# controller.net
KiCad netlist of a schematic drawn in EAGLE
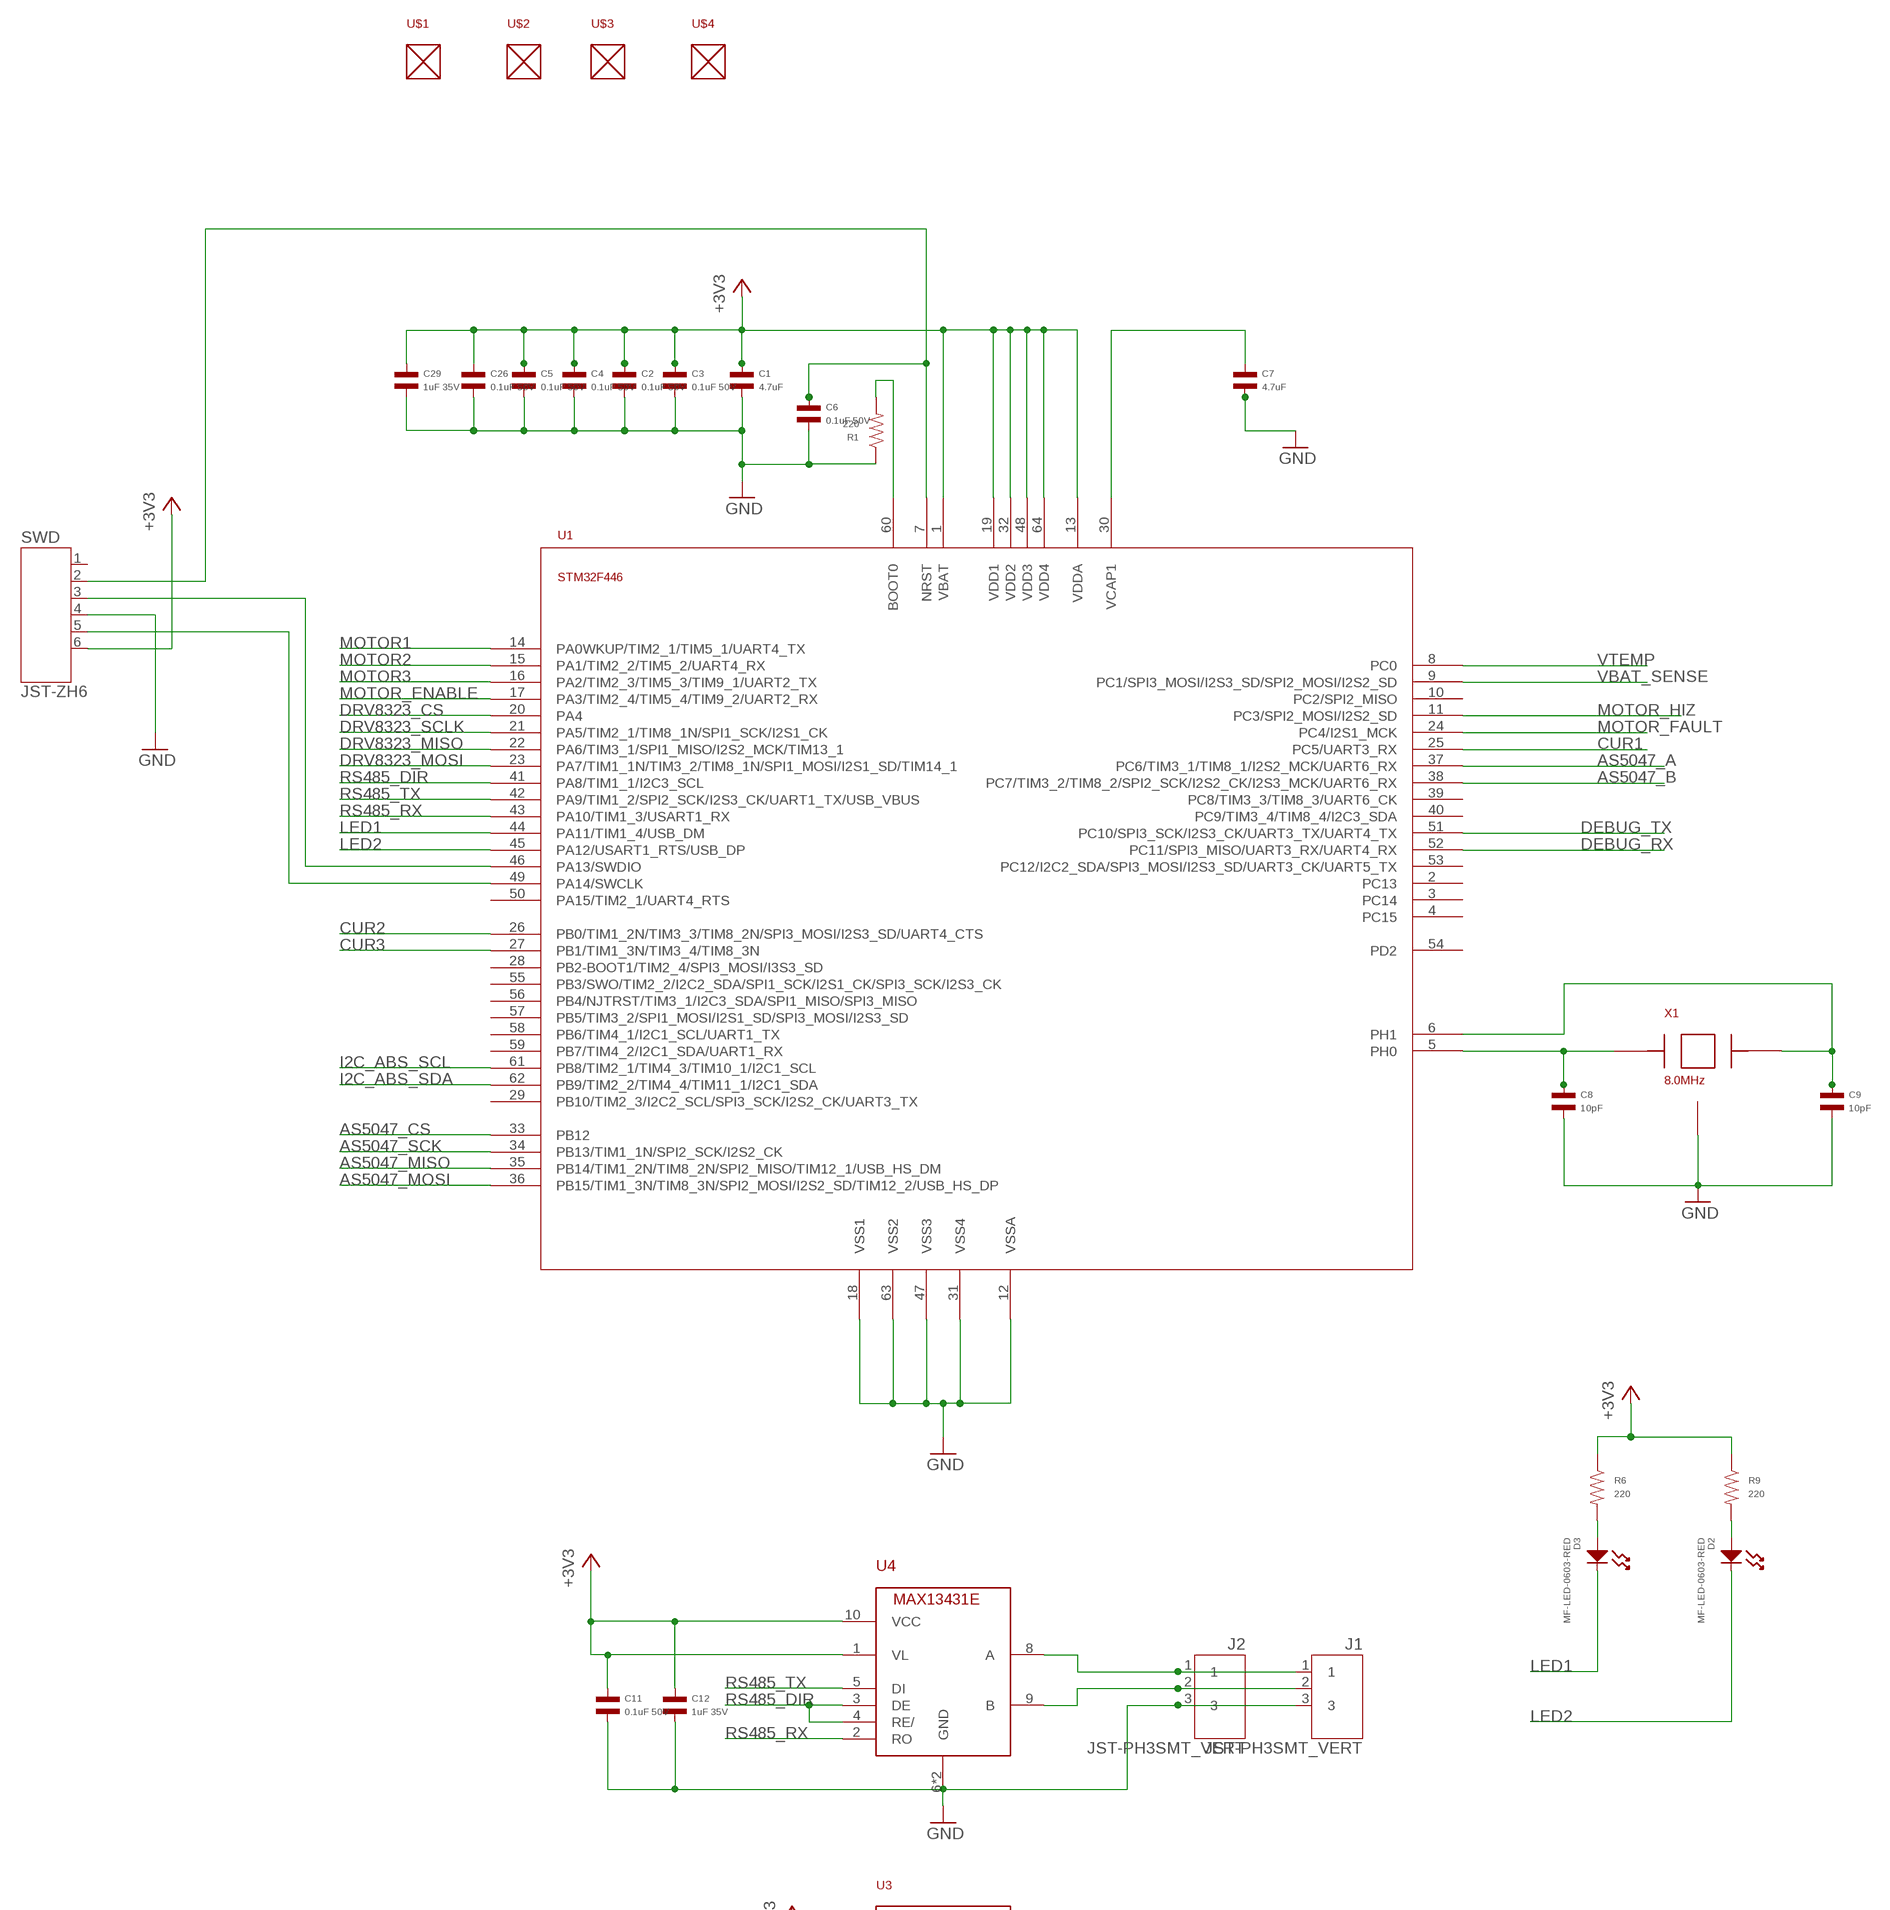
[diagram p0: schematic, sheet 1, part 1 of 2]
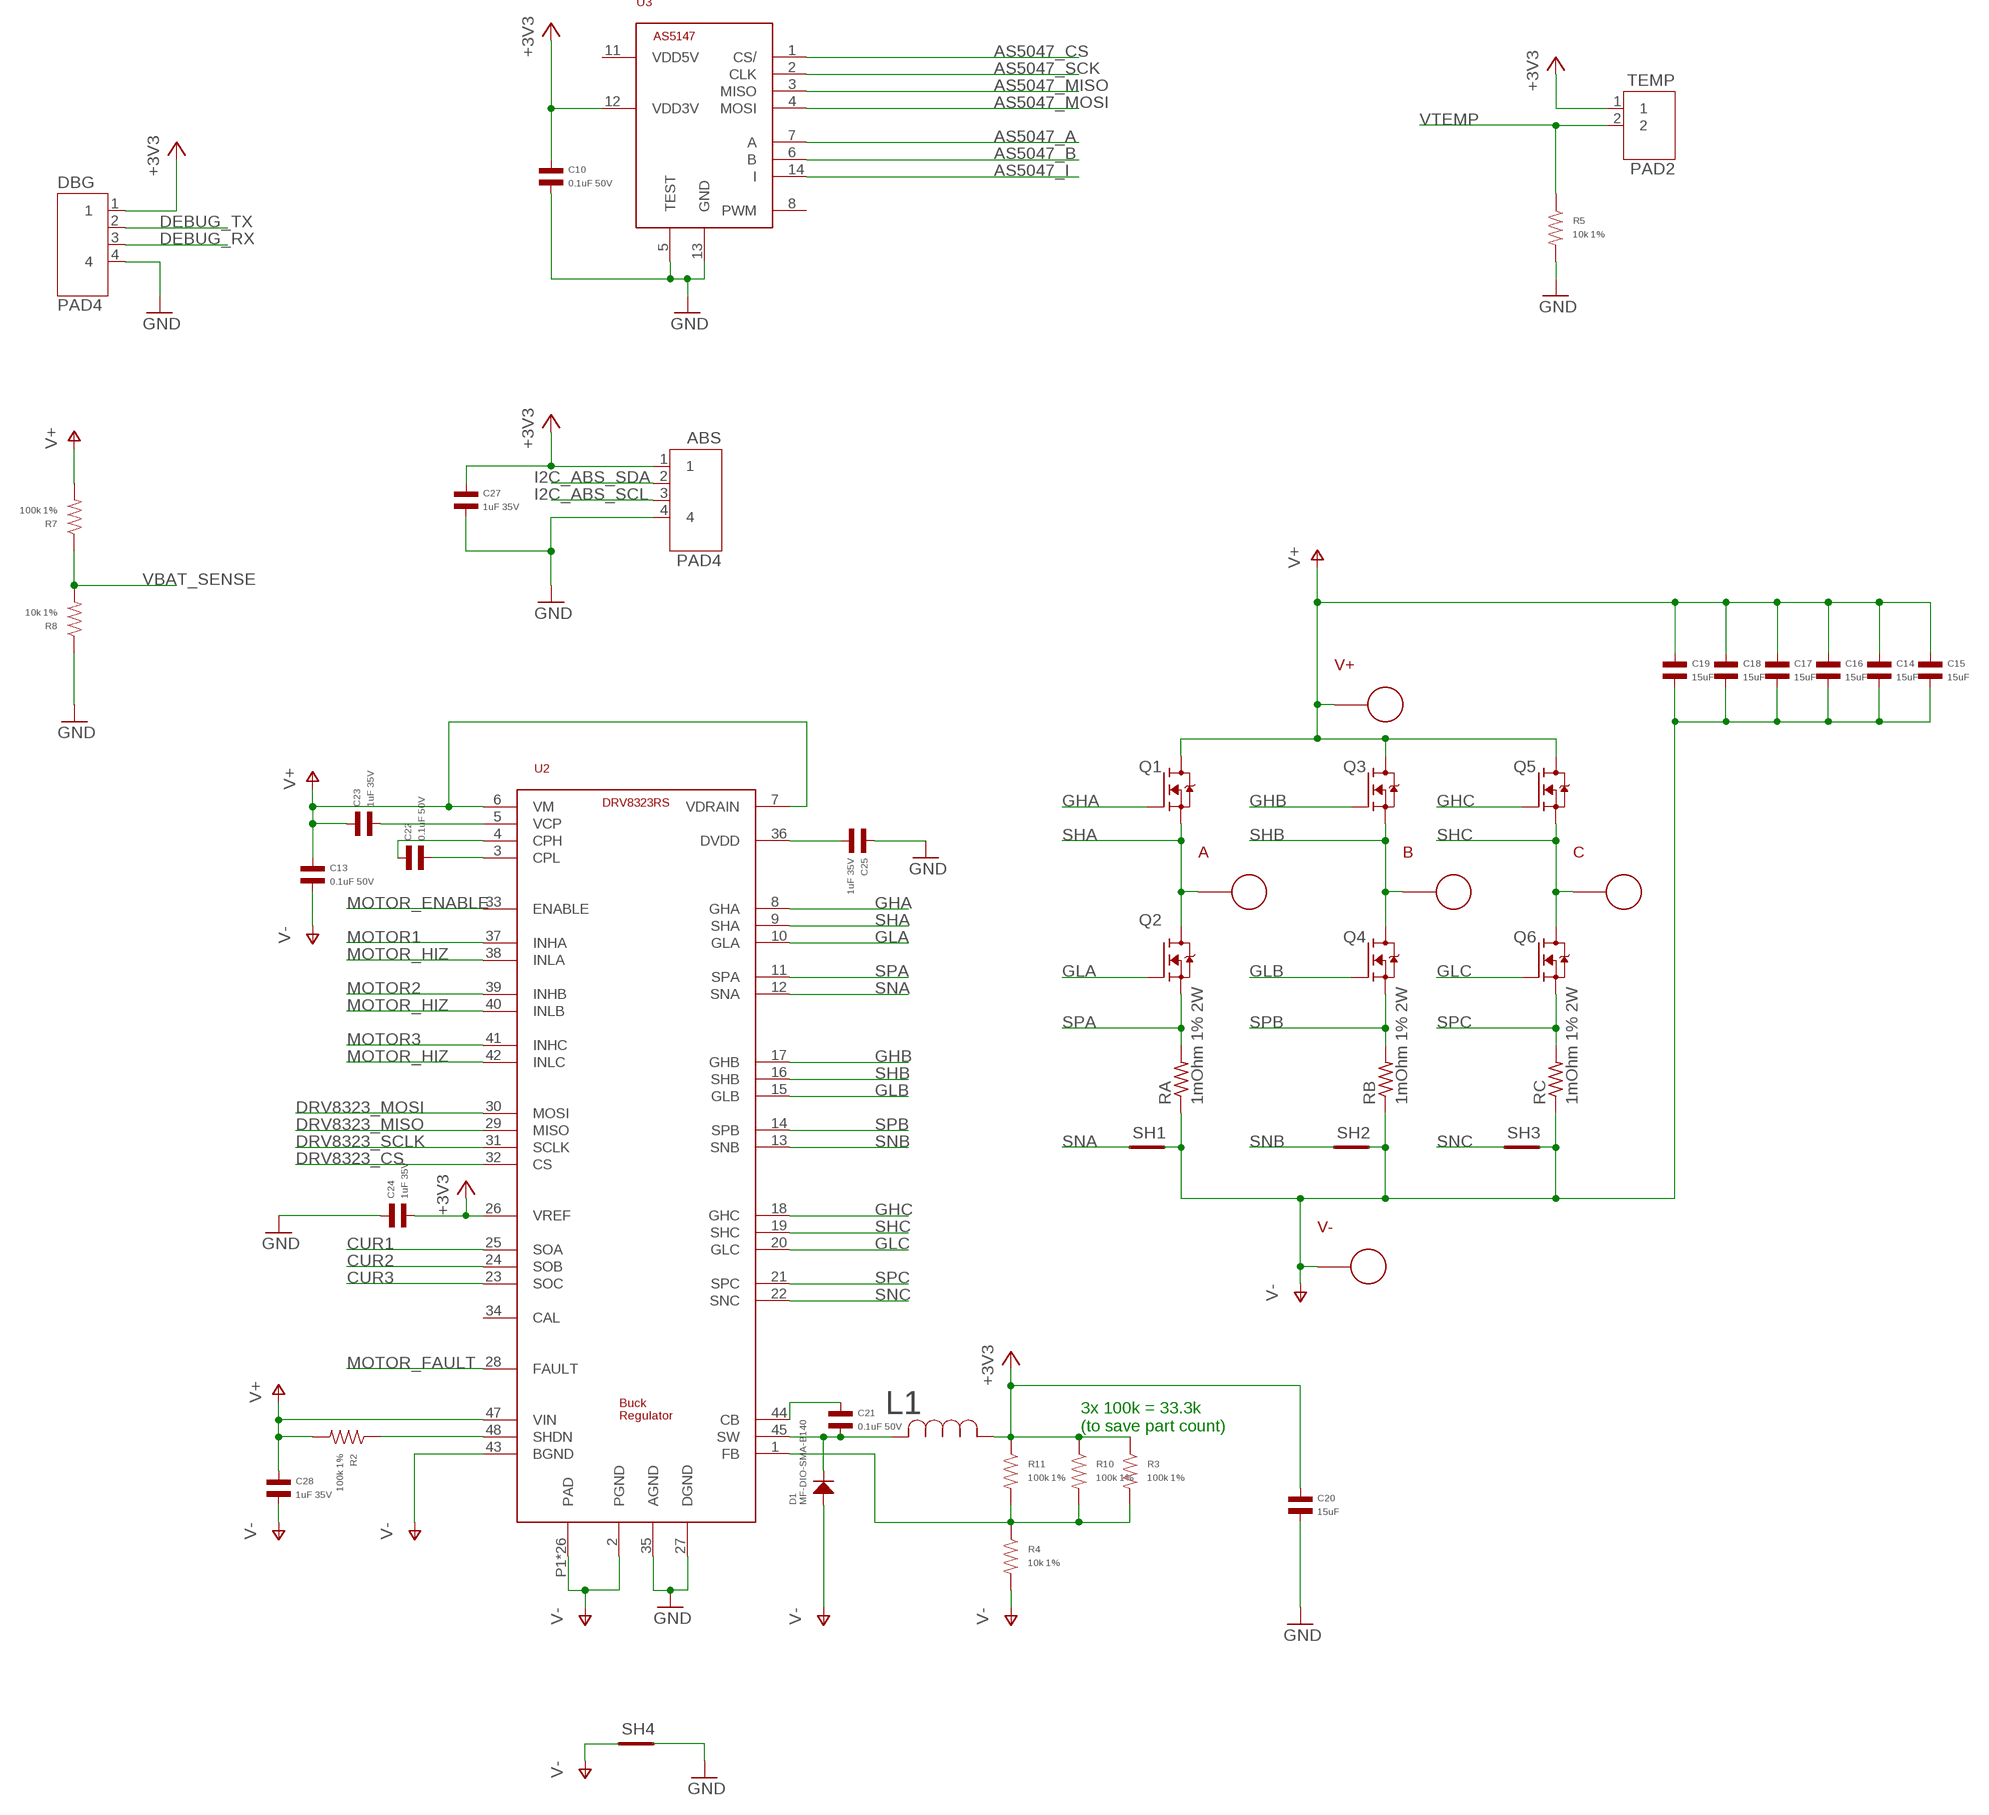
[diagram p1: schematic, sheet 1, part 2 of 2]

(export (version "E")
  (design (tool "Eeschema 10.0.6"))
  (components
    (comp (ref "A")
      (value "PAD")
      (footprint "eagle-import:18AWG_PAD")
      (libsource (lib "eagle-import") (part "PAD"))
    )
    (comp (ref "ABS")
      (value "PAD4")
      (footprint "eagle-import:PAD15_4")
      (libsource (lib "eagle-import") (part "PAD4"))
    )
    (comp (ref "B")
      (value "PAD")
      (footprint "eagle-import:18AWG_PAD")
      (libsource (lib "eagle-import") (part "PAD"))
    )
    (comp (ref "C")
      (value "PAD")
      (footprint "eagle-import:18AWG_PAD")
      (libsource (lib "eagle-import") (part "PAD"))
    )
    (comp (ref "C1")
      (value "4.7uF")
      (footprint "eagle-import:C0603")
      (fields (field (name "MF") "Samsung Electro-Mechanics") (field (name "MPN") "CL10A475MP8NNNC"))
      (libsource (lib "eagle-import") (part "CAPACITOR_NP_0603"))
    )
    (comp (ref "C2")
      (value "0.1uF 50V")
      (footprint "eagle-import:C0402")
      (fields (field (name "MF") "TDK") (field (name "MPN") "C1005X7R1H104K050BE"))
      (libsource (lib "eagle-import") (part "CAPACITOR_NP_0402"))
    )
    (comp (ref "C3")
      (value "0.1uF 50V")
      (footprint "eagle-import:C0402")
      (fields (field (name "MF") "TDK") (field (name "MPN") "C1005X7R1H104K050BE"))
      (libsource (lib "eagle-import") (part "CAPACITOR_NP_0402"))
    )
    (comp (ref "C4")
      (value "0.1uF 50V")
      (footprint "eagle-import:C0402")
      (fields (field (name "MF") "TDK") (field (name "MPN") "C1005X7R1H104K050BE"))
      (libsource (lib "eagle-import") (part "CAPACITOR_NP_0402"))
    )
    (comp (ref "C5")
      (value "0.1uF 50V")
      (footprint "eagle-import:C0402")
      (fields (field (name "MF") "TDK") (field (name "MPN") "C1005X7R1H104K050BE"))
      (libsource (lib "eagle-import") (part "CAPACITOR_NP_0402"))
    )
    (comp (ref "C6")
      (value "0.1uF 50V")
      (footprint "eagle-import:C0402")
      (fields (field (name "MF") "TDK") (field (name "MPN") "C1005X7R1H104K050BE"))
      (libsource (lib "eagle-import") (part "CAPACITOR_NP_0402"))
    )
    (comp (ref "C7")
      (value "4.7uF")
      (footprint "eagle-import:C0603")
      (fields (field (name "MF") "Samsung Electro-Mechanics") (field (name "MPN") "CL10A475MP8NNNC"))
      (libsource (lib "eagle-import") (part "CAPACITOR_NP_0603"))
    )
    (comp (ref "C8")
      (value "10pF")
      (footprint "eagle-import:C0402")
      (fields (field (name "MF") "Samsung Electro-Mechanics") (field (name "MPN") "CL05C100JB51PNC"))
      (libsource (lib "eagle-import") (part "CAPACITOR_NP_0402"))
    )
    (comp (ref "C9")
      (value "10pF")
      (footprint "eagle-import:C0402")
      (fields (field (name "MF") "Samsung Electro-Mechanics") (field (name "MPN") "CL05C100JB51PNC"))
      (libsource (lib "eagle-import") (part "CAPACITOR_NP_0402"))
    )
    (comp (ref "C10")
      (value "0.1uF 50V")
      (footprint "eagle-import:C0402")
      (fields (field (name "MF") "TDK") (field (name "MPN") "C1005X7R1H104K050BE"))
      (libsource (lib "eagle-import") (part "CAPACITOR_NP_0402"))
    )
    (comp (ref "C11")
      (value "0.1uF 50V")
      (footprint "eagle-import:C0402")
      (fields (field (name "MF") "TDK") (field (name "MPN") "C1005X7R1H104K050BE"))
      (libsource (lib "eagle-import") (part "CAPACITOR_NP_0402"))
    )
    (comp (ref "C12")
      (value "1uF 35V")
      (footprint "eagle-import:C0402")
      (fields (field (name "MF") "Samsung Electro-Mechanics") (field (name "MPN") "CL05A105KL5NRNC"))
      (libsource (lib "eagle-import") (part "CAPACITOR_NP_0402"))
    )
    (comp (ref "C13")
      (value "0.1uF 50V")
      (footprint "eagle-import:C0402")
      (fields (field (name "MF") "TDK") (field (name "MPN") "C1005X7R1H104K050BE"))
      (libsource (lib "eagle-import") (part "CAPACITOR_NP_0402"))
    )
    (comp (ref "C14")
      (value "15uF")
      (footprint "eagle-import:C1206")
      (fields (field (name "MF") "TDK") (field (name "MPN") "C3216X5R1V156M160AC"))
      (libsource (lib "eagle-import") (part "CAPACITOR_NP_1206"))
    )
    (comp (ref "C15")
      (value "15uF")
      (footprint "eagle-import:C1206")
      (fields (field (name "MF") "TDK") (field (name "MPN") "C3216X5R1V156M160AC"))
      (libsource (lib "eagle-import") (part "CAPACITOR_NP_1206"))
    )
    (comp (ref "C16")
      (value "15uF")
      (footprint "eagle-import:C1206")
      (fields (field (name "MF") "TDK") (field (name "MPN") "C3216X5R1V156M160AC"))
      (libsource (lib "eagle-import") (part "CAPACITOR_NP_1206"))
    )
    (comp (ref "C17")
      (value "15uF")
      (footprint "eagle-import:C1206")
      (fields (field (name "MF") "TDK") (field (name "MPN") "C3216X5R1V156M160AC"))
      (libsource (lib "eagle-import") (part "CAPACITOR_NP_1206"))
    )
    (comp (ref "C18")
      (value "15uF")
      (footprint "eagle-import:C1206")
      (fields (field (name "MF") "TDK") (field (name "MPN") "C3216X5R1V156M160AC"))
      (libsource (lib "eagle-import") (part "CAPACITOR_NP_1206"))
    )
    (comp (ref "C19")
      (value "15uF")
      (footprint "eagle-import:C1206")
      (fields (field (name "MF") "TDK") (field (name "MPN") "C3216X5R1V156M160AC"))
      (libsource (lib "eagle-import") (part "CAPACITOR_NP_1206"))
    )
    (comp (ref "C20")
      (value "15uF")
      (footprint "eagle-import:C1206")
      (fields (field (name "MF") "TDK") (field (name "MPN") "C3216X5R1V156M160AC"))
      (libsource (lib "eagle-import") (part "CAPACITOR_NP_1206"))
    )
    (comp (ref "C21")
      (value "0.1uF 50V")
      (footprint "eagle-import:C0402")
      (fields (field (name "MF") "TDK") (field (name "MPN") "C1005X7R1H104K050BE"))
      (libsource (lib "eagle-import") (part "CAPACITOR_NP_0402"))
    )
    (comp (ref "C22")
      (value "0.1uF 50V")
      (footprint "eagle-import:C0402")
      (fields (field (name "MF") "TDK") (field (name "MPN") "C1005X7R1H104K050BE"))
      (libsource (lib "eagle-import") (part "CAPACITOR_NP_0402"))
    )
    (comp (ref "C23")
      (value "1uF 35V")
      (footprint "eagle-import:C0402")
      (fields (field (name "MF") "Samsung Electro-Mechanics") (field (name "MPN") "CL05A105KL5NRNC"))
      (libsource (lib "eagle-import") (part "CAPACITOR_NP_0402"))
    )
    (comp (ref "C24")
      (value "1uF 35V")
      (footprint "eagle-import:C0402")
      (fields (field (name "MF") "Samsung Electro-Mechanics") (field (name "MPN") "CL05A105KL5NRNC"))
      (libsource (lib "eagle-import") (part "CAPACITOR_NP_0402"))
    )
    (comp (ref "C25")
      (value "1uF 35V")
      (footprint "eagle-import:C0402")
      (fields (field (name "MF") "Samsung Electro-Mechanics") (field (name "MPN") "CL05A105KL5NRNC"))
      (libsource (lib "eagle-import") (part "CAPACITOR_NP_0402"))
    )
    (comp (ref "C26")
      (value "0.1uF 50V")
      (footprint "eagle-import:C0402")
      (fields (field (name "MF") "TDK") (field (name "MPN") "C1005X7R1H104K050BE"))
      (libsource (lib "eagle-import") (part "CAPACITOR_NP_0402"))
    )
    (comp (ref "C27")
      (value "1uF 35V")
      (footprint "eagle-import:C0402")
      (fields (field (name "MF") "Samsung Electro-Mechanics") (field (name "MPN") "CL05A105KL5NRNC"))
      (libsource (lib "eagle-import") (part "CAPACITOR_NP_0402"))
    )
    (comp (ref "C28")
      (value "1uF 35V")
      (footprint "eagle-import:C0402")
      (fields (field (name "MF") "Samsung Electro-Mechanics") (field (name "MPN") "CL05A105KL5NRNC"))
      (libsource (lib "eagle-import") (part "CAPACITOR_NP_0402"))
    )
    (comp (ref "C29")
      (value "1uF 35V")
      (footprint "eagle-import:C0402")
      (fields (field (name "MF") "Samsung Electro-Mechanics") (field (name "MPN") "CL05A105KL5NRNC"))
      (libsource (lib "eagle-import") (part "CAPACITOR_NP_0402"))
    )
    (comp (ref "D1")
      (value "MF-DIO-SMA-B140")
      (footprint "eagle-import:SMA")
      (fields (field (name "HOUSEPART") "YES"))
      (libsource (lib "eagle-import") (part "DIODES_SMA_B140"))
    )
    (comp (ref "D2")
      (value "MF-LED-0603-RED")
      (footprint "eagle-import:LED0603")
      (fields (field (name "HOUSEPART") "YES"))
      (libsource (lib "eagle-import") (part "LED_SINGLE-0603-RED"))
    )
    (comp (ref "D3")
      (value "MF-LED-0603-RED")
      (footprint "eagle-import:LED0603")
      (fields (field (name "HOUSEPART") "YES"))
      (libsource (lib "eagle-import") (part "LED_SINGLE-0603-RED"))
    )
    (comp (ref "DBG")
      (value "PAD4")
      (footprint "eagle-import:PAD15_4")
      (libsource (lib "eagle-import") (part "PAD4"))
    )
    (comp (ref "J1")
      (value "JST-PH3SMT_VERT")
      (footprint "eagle-import:JST_B3B_PH-SM4-TB(LF)(SN)")
      (fields (field (name "MF") "JST") (field (name "MPN") "B3B-PH-SM4-TB(LF)(SN)"))
      (libsource (lib "eagle-import") (part "JST-PH3SMT_VERT"))
    )
    (comp (ref "J2")
      (value "JST-PH3SMT_VERT")
      (footprint "eagle-import:JST_B3B_PH-SM4-TB(LF)(SN)")
      (fields (field (name "MF") "JST") (field (name "MPN") "B3B-PH-SM4-TB(LF)(SN)"))
      (libsource (lib "eagle-import") (part "JST-PH3SMT_VERT"))
    )
    (comp (ref "L1")
      (value "SRN4018-220M")
      (footprint "eagle-import:IND_BOURNS_SRN4018")
      (fields (field (name "MANUFACTURER_PART_NUMBER") "SRN4018220M"))
      (libsource (lib "eagle-import") (part "SRN4018-220M"))
    )
    (comp (ref "Q1")
      (value "TPN1R603PL")
      (footprint "eagle-import:TSON_ADVANCE_8")
      (fields (field (name "MF") "Toshiba") (field (name "MPN") "TPN1R603PL,L1Q"))
      (libsource (lib "eagle-import") (part "TPN1R603PL"))
    )
    (comp (ref "Q2")
      (value "TPN1R603PL")
      (footprint "eagle-import:TSON_ADVANCE_8")
      (fields (field (name "MF") "Toshiba") (field (name "MPN") "TPN1R603PL,L1Q"))
      (libsource (lib "eagle-import") (part "TPN1R603PL"))
    )
    (comp (ref "Q3")
      (value "TPN1R603PL")
      (footprint "eagle-import:TSON_ADVANCE_8")
      (fields (field (name "MF") "Toshiba") (field (name "MPN") "TPN1R603PL,L1Q"))
      (libsource (lib "eagle-import") (part "TPN1R603PL"))
    )
    (comp (ref "Q4")
      (value "TPN1R603PL")
      (footprint "eagle-import:TSON_ADVANCE_8")
      (fields (field (name "MF") "Toshiba") (field (name "MPN") "TPN1R603PL,L1Q"))
      (libsource (lib "eagle-import") (part "TPN1R603PL"))
    )
    (comp (ref "Q5")
      (value "TPN1R603PL")
      (footprint "eagle-import:TSON_ADVANCE_8")
      (fields (field (name "MF") "Toshiba") (field (name "MPN") "TPN1R603PL,L1Q"))
      (libsource (lib "eagle-import") (part "TPN1R603PL"))
    )
    (comp (ref "Q6")
      (value "TPN1R603PL")
      (footprint "eagle-import:TSON_ADVANCE_8")
      (fields (field (name "MF") "Toshiba") (field (name "MPN") "TPN1R603PL,L1Q"))
      (libsource (lib "eagle-import") (part "TPN1R603PL"))
    )
    (comp (ref "R1")
      (value "220")
      (footprint "eagle-import:R0402")
      (fields (field (name "HOUSEPART") "1") (field (name "MPN") "MF-RES-0402-220"))
      (libsource (lib "eagle-import") (part "RESISTOR_0402"))
    )
    (comp (ref "R2")
      (value "100k 1%")
      (footprint "eagle-import:R0402")
      (fields (field (name "MF") "Panasonic") (field (name "MPN") "ERJ-2RKF1003X"))
      (libsource (lib "eagle-import") (part "RESISTOR_0402"))
    )
    (comp (ref "R3")
      (value "100k 1%")
      (footprint "eagle-import:R0402")
      (fields (field (name "MF") "Panasonic") (field (name "MPN") "ERJ-2RKF1003X"))
      (libsource (lib "eagle-import") (part "RESISTOR_0402"))
    )
    (comp (ref "R4")
      (value "10k 1%")
      (footprint "eagle-import:R0402")
      (fields (field (name "MF") "Panasonic") (field (name "MPN") "ERJ-2RKF1002X"))
      (libsource (lib "eagle-import") (part "RESISTOR_0402"))
    )
    (comp (ref "R5")
      (value "10k 1%")
      (footprint "eagle-import:R0402")
      (fields (field (name "MF") "Panasonic") (field (name "MPN") "ERJ-2RKF1002X"))
      (libsource (lib "eagle-import") (part "RESISTOR_0402"))
    )
    (comp (ref "R6")
      (value "220")
      (footprint "eagle-import:R0402")
      (fields (field (name "HOUSEPART") "1") (field (name "MPN") "MF-RES-0402-220"))
      (libsource (lib "eagle-import") (part "RESISTOR_0402"))
    )
    (comp (ref "R7")
      (value "100k 1%")
      (footprint "eagle-import:R0402")
      (fields (field (name "MF") "Panasonic") (field (name "MPN") "ERJ-2RKF1003X"))
      (libsource (lib "eagle-import") (part "RESISTOR_0402"))
    )
    (comp (ref "R8")
      (value "10k 1%")
      (footprint "eagle-import:R0402")
      (fields (field (name "MF") "Panasonic") (field (name "MPN") "ERJ-2RKF1002X"))
      (libsource (lib "eagle-import") (part "RESISTOR_0402"))
    )
    (comp (ref "R9")
      (value "220")
      (footprint "eagle-import:R0402")
      (fields (field (name "HOUSEPART") "1") (field (name "MPN") "MF-RES-0402-220"))
      (libsource (lib "eagle-import") (part "RESISTOR_0402"))
    )
    (comp (ref "R10")
      (value "100k 1%")
      (footprint "eagle-import:R0402")
      (fields (field (name "MF") "Panasonic") (field (name "MPN") "ERJ-2RKF1003X"))
      (libsource (lib "eagle-import") (part "RESISTOR_0402"))
    )
    (comp (ref "R11")
      (value "100k 1%")
      (footprint "eagle-import:R0402")
      (fields (field (name "MF") "Panasonic") (field (name "MPN") "ERJ-2RKF1003X"))
      (libsource (lib "eagle-import") (part "RESISTOR_0402"))
    )
    (comp (ref "RA")
      (value "1mOhm 1% 2W")
      (footprint "eagle-import:M1206")
      (fields (field (name "MF") "Stackpole Electronics") (field (name "MPN") "HCS1206FT1L00"))
      (libsource (lib "eagle-import") (part "R-US_M1206"))
    )
    (comp (ref "RB")
      (value "1mOhm 1% 2W")
      (footprint "eagle-import:M1206")
      (fields (field (name "MF") "Stackpole Electronics") (field (name "MPN") "HCS1206FT1L00"))
      (libsource (lib "eagle-import") (part "R-US_M1206"))
    )
    (comp (ref "RC")
      (value "1mOhm 1% 2W")
      (footprint "eagle-import:M1206")
      (fields (field (name "MF") "Stackpole Electronics") (field (name "MPN") "HCS1206FT1L00"))
      (libsource (lib "eagle-import") (part "R-US_M1206"))
    )
    (comp (ref "SH1")
      (value "SHORTT5")
      (footprint "eagle-import:SHORT_TOP-50")
      (libsource (lib "eagle-import") (part "SHORTT5"))
    )
    (comp (ref "SH2")
      (value "SHORTT5")
      (footprint "eagle-import:SHORT_TOP-50")
      (libsource (lib "eagle-import") (part "SHORTT5"))
    )
    (comp (ref "SH3")
      (value "SHORTT5")
      (footprint "eagle-import:SHORT_TOP-50")
      (libsource (lib "eagle-import") (part "SHORTT5"))
    )
    (comp (ref "SH4")
      (value "SHORTBIG")
      (footprint "eagle-import:SHORT_TOP-BIG")
      (libsource (lib "eagle-import") (part "SHORTBIG"))
    )
    (comp (ref "SWD")
      (value "JST-ZH6")
      (footprint "eagle-import:JST_S6B-ZR-SM4A-TF(LF)(SN)")
      (fields (field (name "MF") "JST") (field (name "MPN") "S6B-ZR-SM4A-TF(LF)(SN)"))
      (libsource (lib "eagle-import") (part "JST-ZH6"))
    )
    (comp (ref "TEMP")
      (value "PAD2")
      (footprint "eagle-import:PAD15_2")
      (libsource (lib "eagle-import") (part "PAD2"))
    )
    (comp (ref "U$1")
      (value "MOUNTM2")
      (footprint "eagle-import:M2MOUNT")
      (libsource (lib "eagle-import") (part "MOUNTM2"))
    )
    (comp (ref "U$2")
      (value "MOUNTM2")
      (footprint "eagle-import:M2MOUNT")
      (libsource (lib "eagle-import") (part "MOUNTM2"))
    )
    (comp (ref "U$3")
      (value "MOUNTM2")
      (footprint "eagle-import:M2MOUNT")
      (libsource (lib "eagle-import") (part "MOUNTM2"))
    )
    (comp (ref "U$4")
      (value "MOUNTM2")
      (footprint "eagle-import:M2MOUNT")
      (libsource (lib "eagle-import") (part "MOUNTM2"))
    )
    (comp (ref "U1")
      (value "STM32F4R_64PIN")
      (footprint "eagle-import:LQFP64")
      (fields (field (name "MF") "ST") (field (name "MPN") "STM32F446RET6"))
      (libsource (lib "eagle-import") (part "STM32F4R_64PIN"))
    )
    (comp (ref "U2")
      (value "DRV8323RS")
      (footprint "eagle-import:PVQFN-N48")
      (fields (field (name "MF") "TI") (field (name "MPN") "DRV8323RSRGZR"))
      (libsource (lib "eagle-import") (part "DRV8323RS"))
    )
    (comp (ref "U3")
      (value "AS5147")
      (footprint "eagle-import:TSSOP14")
      (fields (field (name "MF") "AMS") (field (name "MPN") "AS5047P-ATSM"))
      (libsource (lib "eagle-import") (part "AS5147"))
    )
    (comp (ref "U4")
      (value "MAX13431E")
      (footprint "eagle-import:TDFN10")
      (fields (field (name "MF") "Maxim") (field (name "MPN") "MAX13431EETB+T"))
      (libsource (lib "eagle-import") (part "MAX13431E"))
    )
    (comp (ref "V+")
      (value "PAD12AWG_PAD")
      (footprint "eagle-import:12AWG_PAD")
      (libsource (lib "eagle-import") (part "PAD12AWG_PAD"))
    )
    (comp (ref "V-")
      (value "PAD12AWG_PAD")
      (footprint "eagle-import:12AWG_PAD")
      (libsource (lib "eagle-import") (part "PAD12AWG_PAD"))
    )
    (comp (ref "X1")
      (value "8.0MHz")
      (footprint "eagle-import:ABM3B")
      (fields (field (name "MF") "Abracon") (field (name "MPN") "ABM3B-8.000MHZ-10-1-U-T"))
      (libsource (lib "eagle-import") (part "CRYSTALABM3B"))
    )
  )
  (nets
    (net (code "1") (name "+3V3") (class "Default")
      (node (ref "ABS") (pin "1") (pinfunction "1_1") (pintype "passive"))
      (node (ref "C1") (pin "P$1") (pinfunction "P$1_P$1") (pintype "passive"))
      (node (ref "C10") (pin "P$1") (pinfunction "P$1_P$1") (pintype "passive"))
      (node (ref "C11") (pin "P$1") (pinfunction "P$1_P$1") (pintype "passive"))
      (node (ref "C12") (pin "P$1") (pinfunction "P$1_P$1") (pintype "passive"))
      (node (ref "C2") (pin "P$1") (pinfunction "P$1_P$1") (pintype "passive"))
      (node (ref "C20") (pin "P$1") (pinfunction "P$1_P$1") (pintype "passive"))
      (node (ref "C24") (pin "P$2") (pinfunction "P$2_P$2") (pintype "passive"))
      (node (ref "C26") (pin "P$1") (pinfunction "P$1_P$1") (pintype "passive"))
      (node (ref "C27") (pin "P$1") (pinfunction "P$1_P$1") (pintype "passive"))
      (node (ref "C29") (pin "P$1") (pinfunction "P$1_P$1") (pintype "passive"))
      (node (ref "C3") (pin "P$1") (pinfunction "P$1_P$1") (pintype "passive"))
      (node (ref "C4") (pin "P$1") (pinfunction "P$1_P$1") (pintype "passive"))
      (node (ref "C5") (pin "P$1") (pinfunction "P$1_P$1") (pintype "passive"))
      (node (ref "DBG") (pin "1") (pinfunction "1_1") (pintype "passive"))
      (node (ref "L1") (pin "1") (pinfunction "1_1") (pintype "passive"))
      (node (ref "R10") (pin "P$1") (pinfunction "P$1_P$1") (pintype "passive"))
      (node (ref "R11") (pin "P$1") (pinfunction "P$1_P$1") (pintype "passive"))
      (node (ref "R3") (pin "P$1") (pinfunction "P$1_P$1") (pintype "passive"))
      (node (ref "R6") (pin "P$1") (pinfunction "P$1_P$1") (pintype "passive"))
      (node (ref "R9") (pin "P$1") (pinfunction "P$1_P$1") (pintype "passive"))
      (node (ref "SWD") (pin "6") (pinfunction "6_6") (pintype "passive"))
      (node (ref "TEMP") (pin "1") (pinfunction "1_1") (pintype "passive"))
      (node (ref "U1") (pin "1") (pinfunction "VBAT_1") (pintype "bidirectional"))
      (node (ref "U1") (pin "13") (pinfunction "VDDA_13") (pintype "bidirectional"))
      (node (ref "U1") (pin "19") (pinfunction "VDD1_19") (pintype "bidirectional"))
      (node (ref "U1") (pin "32") (pinfunction "VDD2_32") (pintype "bidirectional"))
      (node (ref "U1") (pin "48") (pinfunction "VDD3_48") (pintype "bidirectional"))
      (node (ref "U1") (pin "64") (pinfunction "VDD4_64") (pintype "bidirectional"))
      (node (ref "U2") (pin "26") (pinfunction "VREF_26") (pintype "bidirectional"))
      (node (ref "U3") (pin "12") (pinfunction "VDD3V_12") (pintype "bidirectional"))
      (node (ref "U4") (pin "1") (pinfunction "VL_1") (pintype "bidirectional"))
      (node (ref "U4") (pin "10") (pinfunction "VCC_10") (pintype "bidirectional"))
    )
    (net (code "2") (name "/AS5047_A") (class "Default")
      (node (ref "U1") (pin "37") (pinfunction "PC6/TIM3_1/TIM8_1/I2S2_MCK/UART6_RX_37") (pintype "bidirectional"))
      (node (ref "U3") (pin "7") (pinfunction "A_7") (pintype "bidirectional"))
    )
    (net (code "3") (name "/AS5047_B") (class "Default")
      (node (ref "U1") (pin "38") (pinfunction "PC7/TIM3_2/TIM8_2/SPI2_SCK/I2S2_CK/I2S3_MCK/UART6_RX_38") (pintype "bidirectional"))
      (node (ref "U3") (pin "6") (pinfunction "B_6") (pintype "bidirectional"))
    )
    (net (code "4") (name "/AS5047_CS") (class "Default")
      (node (ref "U1") (pin "33") (pinfunction "PB12_33") (pintype "bidirectional"))
      (node (ref "U3") (pin "1") (pinfunction "CS/_1") (pintype "bidirectional"))
    )
    (net (code "5") (name "/AS5047_I") (class "Default")
      (node (ref "U3") (pin "14") (pinfunction "I_14") (pintype "bidirectional"))
    )
    (net (code "6") (name "/AS5047_MISO") (class "Default")
      (node (ref "U1") (pin "35") (pinfunction "PB14/TIM1_2N/TIM8_2N/SPI2_MISO/TIM12_1/USB_HS_DM_35") (pintype "bidirectional"))
      (node (ref "U3") (pin "3") (pinfunction "MISO_3") (pintype "bidirectional"))
    )
    (net (code "7") (name "/AS5047_MOSI") (class "Default")
      (node (ref "U1") (pin "36") (pinfunction "PB15/TIM1_3N/TIM8_3N/SPI2_MOSI/I2S2_SD/TIM12_2/USB_HS_DP_36") (pintype "bidirectional"))
      (node (ref "U3") (pin "4") (pinfunction "MOSI_4") (pintype "bidirectional"))
    )
    (net (code "8") (name "/AS5047_SCK") (class "Default")
      (node (ref "U1") (pin "34") (pinfunction "PB13/TIM1_1N/SPI2_SCK/I2S2_CK_34") (pintype "bidirectional"))
      (node (ref "U3") (pin "2") (pinfunction "CLK_2") (pintype "bidirectional"))
    )
    (net (code "9") (name "/CUR1") (class "Default")
      (node (ref "U1") (pin "25") (pinfunction "PC5/UART3_RX_25") (pintype "bidirectional"))
      (node (ref "U2") (pin "25") (pinfunction "SOA_25") (pintype "bidirectional"))
    )
    (net (code "10") (name "/CUR2") (class "Default")
      (node (ref "U1") (pin "26") (pinfunction "PB0/TIM1_2N/TIM3_3/TIM8_2N/SPI3_MOSI/I2S3_SD/UART4_CTS_26") (pintype "bidirectional"))
      (node (ref "U2") (pin "24") (pinfunction "SOB_24") (pintype "bidirectional"))
    )
    (net (code "11") (name "/CUR3") (class "Default")
      (node (ref "U1") (pin "27") (pinfunction "PB1/TIM1_3N/TIM3_4/TIM8_3N_27") (pintype "bidirectional"))
      (node (ref "U2") (pin "23") (pinfunction "SOC_23") (pintype "bidirectional"))
    )
    (net (code "12") (name "/DEBUG_RX") (class "Default")
      (node (ref "DBG") (pin "3") (pinfunction "3_3") (pintype "passive"))
      (node (ref "U1") (pin "52") (pinfunction "PC11/SPI3_MISO/UART3_RX/UART4_RX_52") (pintype "bidirectional"))
    )
    (net (code "13") (name "/DEBUG_TX") (class "Default")
      (node (ref "DBG") (pin "2") (pinfunction "2_2") (pintype "passive"))
      (node (ref "U1") (pin "51") (pinfunction "PC10/SPI3_SCK/I2S3_CK/UART3_TX/UART4_TX_51") (pintype "bidirectional"))
    )
    (net (code "14") (name "/DRV8323_CS") (class "Default")
      (node (ref "U1") (pin "20") (pinfunction "PA4_20") (pintype "bidirectional"))
      (node (ref "U2") (pin "32") (pinfunction "CS_32") (pintype "bidirectional"))
    )
    (net (code "15") (name "/DRV8323_MISO") (class "Default")
      (node (ref "U1") (pin "22") (pinfunction "PA6/TIM3_1/SPI1_MISO/I2S2_MCK/TIM13_1_22") (pintype "bidirectional"))
      (node (ref "U2") (pin "29") (pinfunction "MISO_29") (pintype "bidirectional"))
    )
    (net (code "16") (name "/DRV8323_MOSI") (class "Default")
      (node (ref "U1") (pin "23") (pinfunction "PA7/TIM1_1N/TIM3_2/TIM8_1N/SPI1_MOSI/I2S1_SD/TIM14_1_23") (pintype "bidirectional"))
      (node (ref "U2") (pin "30") (pinfunction "MOSI_30") (pintype "bidirectional"))
    )
    (net (code "17") (name "/DRV8323_SCLK") (class "Default")
      (node (ref "U1") (pin "21") (pinfunction "PA5/TIM2_1/TIM8_1N/SPI1_SCK/I2S1_CK_21") (pintype "bidirectional"))
      (node (ref "U2") (pin "31") (pinfunction "SCLK_31") (pintype "bidirectional"))
    )
    (net (code "18") (name "/GHA") (class "Default")
      (node (ref "Q1") (pin "4") (pinfunction "G_4") (pintype "passive"))
      (node (ref "U2") (pin "8") (pinfunction "GHA_8") (pintype "bidirectional"))
    )
    (net (code "19") (name "/GHB") (class "Default")
      (node (ref "Q3") (pin "4") (pinfunction "G_4") (pintype "passive"))
      (node (ref "U2") (pin "17") (pinfunction "GHB_17") (pintype "bidirectional"))
    )
    (net (code "20") (name "/GHC") (class "Default")
      (node (ref "Q5") (pin "4") (pinfunction "G_4") (pintype "passive"))
      (node (ref "U2") (pin "18") (pinfunction "GHC_18") (pintype "bidirectional"))
    )
    (net (code "21") (name "/GLA") (class "Default")
      (node (ref "Q2") (pin "4") (pinfunction "G_4") (pintype "passive"))
      (node (ref "U2") (pin "10") (pinfunction "GLA_10") (pintype "bidirectional"))
    )
    (net (code "22") (name "/GLB") (class "Default")
      (node (ref "Q4") (pin "4") (pinfunction "G_4") (pintype "passive"))
      (node (ref "U2") (pin "15") (pinfunction "GLB_15") (pintype "bidirectional"))
    )
    (net (code "23") (name "/GLC") (class "Default")
      (node (ref "Q6") (pin "4") (pinfunction "G_4") (pintype "passive"))
      (node (ref "U2") (pin "20") (pinfunction "GLC_20") (pintype "bidirectional"))
    )
    (net (code "24") (name "/I2C_ABS_SCL") (class "Default")
      (node (ref "ABS") (pin "3") (pinfunction "3_3") (pintype "passive"))
      (node (ref "U1") (pin "61") (pinfunction "PB8/TIM2_1/TIM4_3/TIM10_1/I2C1_SCL_61") (pintype "bidirectional"))
    )
    (net (code "25") (name "/I2C_ABS_SDA") (class "Default")
      (node (ref "ABS") (pin "2") (pinfunction "2_2") (pintype "passive"))
      (node (ref "U1") (pin "62") (pinfunction "PB9/TIM2_2/TIM4_4/TIM11_1/I2C1_SDA_62") (pintype "bidirectional"))
    )
    (net (code "26") (name "/LED1") (class "Default")
      (node (ref "D3") (pin "CATHODE") (pinfunction "CATHODE_CATHODE") (pintype "power_in"))
      (node (ref "U1") (pin "44") (pinfunction "PA11/TIM1_4/USB_DM_44") (pintype "bidirectional"))
    )
    (net (code "27") (name "/LED2") (class "Default")
      (node (ref "D2") (pin "CATHODE") (pinfunction "CATHODE_CATHODE") (pintype "power_in"))
      (node (ref "U1") (pin "45") (pinfunction "PA12/USART1_RTS/USB_DP_45") (pintype "bidirectional"))
    )
    (net (code "28") (name "/MOTOR1") (class "Default")
      (node (ref "U1") (pin "14") (pinfunction "PA0WKUP/TIM2_1/TIM5_1/UART4_TX_14") (pintype "bidirectional"))
      (node (ref "U2") (pin "37") (pinfunction "INHA_37") (pintype "bidirectional"))
    )
    (net (code "29") (name "/MOTOR2") (class "Default")
      (node (ref "U1") (pin "15") (pinfunction "PA1/TIM2_2/TIM5_2/UART4_RX_15") (pintype "bidirectional"))
      (node (ref "U2") (pin "39") (pinfunction "INHB_39") (pintype "bidirectional"))
    )
    (net (code "30") (name "/MOTOR3") (class "Default")
      (node (ref "U1") (pin "16") (pinfunction "PA2/TIM2_3/TIM5_3/TIM9_1/UART2_TX_16") (pintype "bidirectional"))
      (node (ref "U2") (pin "41") (pinfunction "INHC_41") (pintype "bidirectional"))
    )
    (net (code "31") (name "/MOTOR_ENABLE") (class "Default")
      (node (ref "U1") (pin "17") (pinfunction "PA3/TIM2_4/TIM5_4/TIM9_2/UART2_RX_17") (pintype "bidirectional"))
      (node (ref "U2") (pin "33") (pinfunction "ENABLE_33") (pintype "bidirectional"))
    )
    (net (code "32") (name "/MOTOR_FAULT") (class "Default")
      (node (ref "U1") (pin "24") (pinfunction "PC4/I2S1_MCK_24") (pintype "bidirectional"))
      (node (ref "U2") (pin "28") (pinfunction "FAULT_28") (pintype "bidirectional"))
    )
    (net (code "33") (name "/MOTOR_HIZ") (class "Default")
      (node (ref "U1") (pin "11") (pinfunction "PC3/SPI2_MOSI/I2S2_SD_11") (pintype "bidirectional"))
      (node (ref "U2") (pin "38") (pinfunction "INLA_38") (pintype "bidirectional"))
      (node (ref "U2") (pin "40") (pinfunction "INLB_40") (pintype "bidirectional"))
      (node (ref "U2") (pin "42") (pinfunction "INLC_42") (pintype "bidirectional"))
    )
    (net (code "34") (name "/RS485_DIR") (class "Default")
      (node (ref "U1") (pin "41") (pinfunction "PA8/TIM1_1/I2C3_SCL_41") (pintype "bidirectional"))
      (node (ref "U4") (pin "3") (pinfunction "DE_3") (pintype "bidirectional"))
      (node (ref "U4") (pin "4") (pinfunction "RE/_4") (pintype "bidirectional"))
    )
    (net (code "35") (name "/RS485_RX") (class "Default")
      (node (ref "U1") (pin "43") (pinfunction "PA10/TIM1_3/USART1_RX_43") (pintype "bidirectional"))
      (node (ref "U4") (pin "2") (pinfunction "RO_2") (pintype "bidirectional"))
    )
    (net (code "36") (name "/RS485_TX") (class "Default")
      (node (ref "U1") (pin "42") (pinfunction "PA9/TIM1_2/SPI2_SCK/I2S3_CK/UART1_TX/USB_VBUS_42") (pintype "bidirectional"))
      (node (ref "U4") (pin "5") (pinfunction "DI_5") (pintype "bidirectional"))
    )
    (net (code "37") (name "/SHA") (class "Default")
      (node (ref "A") (pin "1") (pinfunction "P$1_1") (pintype "bidirectional"))
      (node (ref "Q1") (pin "1") (pinfunction "S_1") (pintype "passive"))
      (node (ref "Q1") (pin "2") (pinfunction "S_2") (pintype "passive"))
      (node (ref "Q1") (pin "3") (pinfunction "S_3") (pintype "passive"))
      (node (ref "Q2") (pin "5") (pinfunction "D_5") (pintype "passive"))
      (node (ref "Q2") (pin "6") (pinfunction "D_6") (pintype "passive"))
      (node (ref "Q2") (pin "7") (pinfunction "D_7") (pintype "passive"))
      (node (ref "Q2") (pin "8") (pinfunction "D_8") (pintype "passive"))
      (node (ref "Q2") (pin "PAD") (pinfunction "D_PAD") (pintype "passive"))
      (node (ref "U2") (pin "9") (pinfunction "SHA_9") (pintype "bidirectional"))
    )
    (net (code "38") (name "/SHB") (class "Default")
      (node (ref "B") (pin "1") (pinfunction "P$1_1") (pintype "bidirectional"))
      (node (ref "Q3") (pin "1") (pinfunction "S_1") (pintype "passive"))
      (node (ref "Q3") (pin "2") (pinfunction "S_2") (pintype "passive"))
      (node (ref "Q3") (pin "3") (pinfunction "S_3") (pintype "passive"))
      (node (ref "Q4") (pin "5") (pinfunction "D_5") (pintype "passive"))
      (node (ref "Q4") (pin "6") (pinfunction "D_6") (pintype "passive"))
      (node (ref "Q4") (pin "7") (pinfunction "D_7") (pintype "passive"))
      (node (ref "Q4") (pin "8") (pinfunction "D_8") (pintype "passive"))
      (node (ref "Q4") (pin "PAD") (pinfunction "D_PAD") (pintype "passive"))
      (node (ref "U2") (pin "16") (pinfunction "SHB_16") (pintype "bidirectional"))
    )
    (net (code "39") (name "/SHC") (class "Default")
      (node (ref "C") (pin "1") (pinfunction "P$1_1") (pintype "bidirectional"))
      (node (ref "Q5") (pin "1") (pinfunction "S_1") (pintype "passive"))
      (node (ref "Q5") (pin "2") (pinfunction "S_2") (pintype "passive"))
      (node (ref "Q5") (pin "3") (pinfunction "S_3") (pintype "passive"))
      (node (ref "Q6") (pin "5") (pinfunction "D_5") (pintype "passive"))
      (node (ref "Q6") (pin "6") (pinfunction "D_6") (pintype "passive"))
      (node (ref "Q6") (pin "7") (pinfunction "D_7") (pintype "passive"))
      (node (ref "Q6") (pin "8") (pinfunction "D_8") (pintype "passive"))
      (node (ref "Q6") (pin "PAD") (pinfunction "D_PAD") (pintype "passive"))
      (node (ref "U2") (pin "19") (pinfunction "SHC_19") (pintype "bidirectional"))
    )
    (net (code "40") (name "/SNA") (class "Default")
      (node (ref "SH1") (pin "1") (pinfunction "P$1_1") (pintype "bidirectional"))
      (node (ref "U2") (pin "12") (pinfunction "SNA_12") (pintype "bidirectional"))
    )
    (net (code "41") (name "/SNB") (class "Default")
      (node (ref "SH2") (pin "1") (pinfunction "P$1_1") (pintype "bidirectional"))
      (node (ref "U2") (pin "13") (pinfunction "SNB_13") (pintype "bidirectional"))
    )
    (net (code "42") (name "/SNC") (class "Default")
      (node (ref "SH3") (pin "1") (pinfunction "P$1_1") (pintype "bidirectional"))
      (node (ref "U2") (pin "22") (pinfunction "SNC_22") (pintype "bidirectional"))
    )
    (net (code "43") (name "/SPA") (class "Default")
      (node (ref "Q2") (pin "1") (pinfunction "S_1") (pintype "passive"))
      (node (ref "Q2") (pin "2") (pinfunction "S_2") (pintype "passive"))
      (node (ref "Q2") (pin "3") (pinfunction "S_3") (pintype "passive"))
      (node (ref "RA") (pin "2") (pinfunction "2_2") (pintype "passive"))
      (node (ref "U2") (pin "11") (pinfunction "SPA_11") (pintype "bidirectional"))
    )
    (net (code "44") (name "/SPB") (class "Default")
      (node (ref "Q4") (pin "1") (pinfunction "S_1") (pintype "passive"))
      (node (ref "Q4") (pin "2") (pinfunction "S_2") (pintype "passive"))
      (node (ref "Q4") (pin "3") (pinfunction "S_3") (pintype "passive"))
      (node (ref "RB") (pin "2") (pinfunction "2_2") (pintype "passive"))
      (node (ref "U2") (pin "14") (pinfunction "SPB_14") (pintype "bidirectional"))
    )
    (net (code "45") (name "/SPC") (class "Default")
      (node (ref "Q6") (pin "1") (pinfunction "S_1") (pintype "passive"))
      (node (ref "Q6") (pin "2") (pinfunction "S_2") (pintype "passive"))
      (node (ref "Q6") (pin "3") (pinfunction "S_3") (pintype "passive"))
      (node (ref "RC") (pin "2") (pinfunction "2_2") (pintype "passive"))
      (node (ref "U2") (pin "21") (pinfunction "SPC_21") (pintype "bidirectional"))
    )
    (net (code "46") (name "/VBAT_SENSE") (class "Default")
      (node (ref "R7") (pin "P$1") (pinfunction "P$1_P$1") (pintype "passive"))
      (node (ref "R8") (pin "P$2") (pinfunction "P$2_P$2") (pintype "passive"))
      (node (ref "U1") (pin "9") (pinfunction "PC1/SPI3_MOSI/I2S3_SD/SPI2_MOSI/I2S2_SD_9") (pintype "bidirectional"))
    )
    (net (code "47") (name "/VTEMP") (class "Default")
      (node (ref "R5") (pin "P$1") (pinfunction "P$1_P$1") (pintype "passive"))
      (node (ref "TEMP") (pin "2") (pinfunction "2_2") (pintype "passive"))
      (node (ref "U1") (pin "8") (pinfunction "PC0_8") (pintype "bidirectional"))
    )
    (net (code "48") (name "GND") (class "Default")
      (node (ref "ABS") (pin "4") (pinfunction "4_4") (pintype "passive"))
      (node (ref "C1") (pin "P$2") (pinfunction "P$2_P$2") (pintype "passive"))
      (node (ref "C10") (pin "P$2") (pinfunction "P$2_P$2") (pintype "passive"))
      (node (ref "C11") (pin "P$2") (pinfunction "P$2_P$2") (pintype "passive"))
      (node (ref "C12") (pin "P$2") (pinfunction "P$2_P$2") (pintype "passive"))
      (node (ref "C2") (pin "P$2") (pinfunction "P$2_P$2") (pintype "passive"))
      (node (ref "C20") (pin "P$2") (pinfunction "P$2_P$2") (pintype "passive"))
      (node (ref "C24") (pin "P$1") (pinfunction "P$1_P$1") (pintype "passive"))
      (node (ref "C25") (pin "P$1") (pinfunction "P$1_P$1") (pintype "passive"))
      (node (ref "C26") (pin "P$2") (pinfunction "P$2_P$2") (pintype "passive"))
      (node (ref "C27") (pin "P$2") (pinfunction "P$2_P$2") (pintype "passive"))
      (node (ref "C29") (pin "P$2") (pinfunction "P$2_P$2") (pintype "passive"))
      (node (ref "C3") (pin "P$2") (pinfunction "P$2_P$2") (pintype "passive"))
      (node (ref "C4") (pin "P$2") (pinfunction "P$2_P$2") (pintype "passive"))
      (node (ref "C5") (pin "P$2") (pinfunction "P$2_P$2") (pintype "passive"))
      (node (ref "C6") (pin "P$2") (pinfunction "P$2_P$2") (pintype "passive"))
      (node (ref "C7") (pin "P$2") (pinfunction "P$2_P$2") (pintype "passive"))
      (node (ref "C8") (pin "P$2") (pinfunction "P$2_P$2") (pintype "passive"))
      (node (ref "C9") (pin "P$2") (pinfunction "P$2_P$2") (pintype "passive"))
      (node (ref "DBG") (pin "4") (pinfunction "4_4") (pintype "passive"))
      (node (ref "J1") (pin "3") (pinfunction "3_3") (pintype "passive"))
      (node (ref "J2") (pin "3") (pinfunction "3_3") (pintype "passive"))
      (node (ref "R1") (pin "P$1") (pinfunction "P$1_P$1") (pintype "passive"))
      (node (ref "R5") (pin "P$2") (pinfunction "P$2_P$2") (pintype "passive"))
      (node (ref "R8") (pin "P$1") (pinfunction "P$1_P$1") (pintype "passive"))
      (node (ref "SH4") (pin "2") (pinfunction "P$2_2") (pintype "bidirectional"))
      (node (ref "SWD") (pin "4") (pinfunction "4_4") (pintype "passive"))
      (node (ref "U1") (pin "12") (pinfunction "VSSA_12") (pintype "bidirectional"))
      (node (ref "U1") (pin "18") (pinfunction "VSS1_18") (pintype "bidirectional"))
      (node (ref "U1") (pin "31") (pinfunction "VSS4_31") (pintype "bidirectional"))
      (node (ref "U1") (pin "47") (pinfunction "VSS3_47") (pintype "bidirectional"))
      (node (ref "U1") (pin "63") (pinfunction "VSS2_63") (pintype "bidirectional"))
      (node (ref "U2") (pin "27") (pinfunction "DGND_27") (pintype "bidirectional"))
      (node (ref "U2") (pin "35") (pinfunction "AGND_35") (pintype "bidirectional"))
      (node (ref "U3") (pin "13") (pinfunction "GND_13") (pintype "bidirectional"))
      (node (ref "U3") (pin "5") (pinfunction "TEST_5") (pintype "bidirectional"))
      (node (ref "U4") (pin "6") (pinfunction "GND_6") (pintype "bidirectional"))
      (node (ref "U4") (pin "PAD") (pinfunction "GND_PAD") (pintype "bidirectional"))
      (node (ref "X1") (pin "2") (pinfunction "P$3_2") (pintype "bidirectional"))
      (node (ref "X1") (pin "4") (pinfunction "P$3_4") (pintype "bidirectional"))
    )
    (net (code "49") (name "Net-(D2-PadANODE)") (class "Default")
      (node (ref "D2") (pin "ANODE") (pinfunction "ANODE_ANODE") (pintype "power_in"))
      (node (ref "R9") (pin "P$2") (pinfunction "P$2_P$2") (pintype "passive"))
    )
    (net (code "50") (name "Net-(D3-PadANODE)") (class "Default")
      (node (ref "D3") (pin "ANODE") (pinfunction "ANODE_ANODE") (pintype "power_in"))
      (node (ref "R6") (pin "P$2") (pinfunction "P$2_P$2") (pintype "passive"))
    )
    (net (code "51") (name "Net-(U1-BOOT0)") (class "Default")
      (node (ref "R1") (pin "P$2") (pinfunction "P$2_P$2") (pintype "passive"))
      (node (ref "U1") (pin "60") (pinfunction "BOOT0_60") (pintype "bidirectional"))
    )
    (net (code "52") (name "Net-(U1-NRST)") (class "Default")
      (node (ref "C6") (pin "P$1") (pinfunction "P$1_P$1") (pintype "passive"))
      (node (ref "SWD") (pin "2") (pinfunction "2_2") (pintype "passive"))
      (node (ref "U1") (pin "7") (pinfunction "NRST_7") (pintype "bidirectional"))
    )
    (net (code "53") (name "Net-(U1-PA13{slash}SWDIO)") (class "Default")
      (node (ref "SWD") (pin "3") (pinfunction "3_3") (pintype "passive"))
      (node (ref "U1") (pin "46") (pinfunction "PA13/SWDIO_46") (pintype "bidirectional"))
    )
    (net (code "54") (name "Net-(U1-PA14{slash}SWCLK)") (class "Default")
      (node (ref "SWD") (pin "5") (pinfunction "5_5") (pintype "passive"))
      (node (ref "U1") (pin "49") (pinfunction "PA14/SWCLK_49") (pintype "bidirectional"))
    )
    (net (code "55") (name "Net-(U1-PH0)") (class "Default")
      (node (ref "C8") (pin "P$1") (pinfunction "P$1_P$1") (pintype "passive"))
      (node (ref "U1") (pin "5") (pinfunction "PH0_5") (pintype "bidirectional"))
      (node (ref "X1") (pin "1") (pinfunction "P$1_1") (pintype "bidirectional"))
    )
    (net (code "56") (name "Net-(U1-PH1)") (class "Default")
      (node (ref "C9") (pin "P$1") (pinfunction "P$1_P$1") (pintype "passive"))
      (node (ref "U1") (pin "6") (pinfunction "PH1_6") (pintype "bidirectional"))
      (node (ref "X1") (pin "3") (pinfunction "P$2_3") (pintype "bidirectional"))
    )
    (net (code "57") (name "Net-(U1-VCAP1)") (class "Default")
      (node (ref "C7") (pin "P$1") (pinfunction "P$1_P$1") (pintype "passive"))
      (node (ref "U1") (pin "30") (pinfunction "VCAP1_30") (pintype "bidirectional"))
    )
    (net (code "58") (name "Net-(U2-CB)") (class "Default")
      (node (ref "C21") (pin "P$1") (pinfunction "P$1_P$1") (pintype "passive"))
      (node (ref "U2") (pin "44") (pinfunction "CB_44") (pintype "bidirectional"))
    )
    (net (code "59") (name "Net-(U2-CPH)") (class "Default")
      (node (ref "C22") (pin "P$1") (pinfunction "P$1_P$1") (pintype "passive"))
      (node (ref "U2") (pin "4") (pinfunction "CPH_4") (pintype "bidirectional"))
    )
    (net (code "60") (name "Net-(U2-CPL)") (class "Default")
      (node (ref "C22") (pin "P$2") (pinfunction "P$2_P$2") (pintype "passive"))
      (node (ref "U2") (pin "3") (pinfunction "CPL_3") (pintype "bidirectional"))
    )
    (net (code "61") (name "Net-(U2-DVDD)") (class "Default")
      (node (ref "C25") (pin "P$2") (pinfunction "P$2_P$2") (pintype "passive"))
      (node (ref "U2") (pin "36") (pinfunction "DVDD_36") (pintype "bidirectional"))
    )
    (net (code "62") (name "Net-(U2-FB)") (class "Default")
      (node (ref "R10") (pin "P$2") (pinfunction "P$2_P$2") (pintype "passive"))
      (node (ref "R11") (pin "P$2") (pinfunction "P$2_P$2") (pintype "passive"))
      (node (ref "R3") (pin "P$2") (pinfunction "P$2_P$2") (pintype "passive"))
      (node (ref "R4") (pin "P$1") (pinfunction "P$1_P$1") (pintype "passive"))
      (node (ref "U2") (pin "1") (pinfunction "FB_1") (pintype "bidirectional"))
    )
    (net (code "63") (name "Net-(U2-SHDN)") (class "Default")
      (node (ref "R2") (pin "P$1") (pinfunction "P$1_P$1") (pintype "passive"))
      (node (ref "U2") (pin "48") (pinfunction "SHDN_48") (pintype "bidirectional"))
    )
    (net (code "64") (name "Net-(U2-SW)") (class "Default")
      (node (ref "C21") (pin "P$2") (pinfunction "P$2_P$2") (pintype "passive"))
      (node (ref "D1") (pin "CATHODE") (pinfunction "CATHODE_CATHODE") (pintype "bidirectional"))
      (node (ref "L1") (pin "2") (pinfunction "2_2") (pintype "passive"))
      (node (ref "U2") (pin "45") (pinfunction "SW_45") (pintype "bidirectional"))
    )
    (net (code "65") (name "Net-(U2-VCP)") (class "Default")
      (node (ref "C23") (pin "P$2") (pinfunction "P$2_P$2") (pintype "passive"))
      (node (ref "U2") (pin "5") (pinfunction "VCP_5") (pintype "bidirectional"))
    )
    (net (code "66") (name "Net-(U4-A)") (class "Default")
      (node (ref "J1") (pin "1") (pinfunction "1_1") (pintype "passive"))
      (node (ref "J2") (pin "1") (pinfunction "1_1") (pintype "passive"))
      (node (ref "U4") (pin "8") (pinfunction "A_8") (pintype "bidirectional"))
    )
    (net (code "67") (name "Net-(U4-B)") (class "Default")
      (node (ref "J1") (pin "2") (pinfunction "2_2") (pintype "passive"))
      (node (ref "J2") (pin "2") (pinfunction "2_2") (pintype "passive"))
      (node (ref "U4") (pin "9") (pinfunction "B_9") (pintype "bidirectional"))
    )
    (net (code "68") (name "V+") (class "Default")
      (node (ref "C13") (pin "P$1") (pinfunction "P$1_P$1") (pintype "passive"))
      (node (ref "C14") (pin "P$1") (pinfunction "P$1_P$1") (pintype "passive"))
      (node (ref "C15") (pin "P$1") (pinfunction "P$1_P$1") (pintype "passive"))
      (node (ref "C16") (pin "P$1") (pinfunction "P$1_P$1") (pintype "passive"))
      (node (ref "C17") (pin "P$1") (pinfunction "P$1_P$1") (pintype "passive"))
      (node (ref "C18") (pin "P$1") (pinfunction "P$1_P$1") (pintype "passive"))
      (node (ref "C19") (pin "P$1") (pinfunction "P$1_P$1") (pintype "passive"))
      (node (ref "C23") (pin "P$1") (pinfunction "P$1_P$1") (pintype "passive"))
      (node (ref "C28") (pin "P$1") (pinfunction "P$1_P$1") (pintype "passive"))
      (node (ref "Q1") (pin "5") (pinfunction "D_5") (pintype "passive"))
      (node (ref "Q1") (pin "6") (pinfunction "D_6") (pintype "passive"))
      (node (ref "Q1") (pin "7") (pinfunction "D_7") (pintype "passive"))
      (node (ref "Q1") (pin "8") (pinfunction "D_8") (pintype "passive"))
      (node (ref "Q1") (pin "PAD") (pinfunction "D_PAD") (pintype "passive"))
      (node (ref "Q3") (pin "5") (pinfunction "D_5") (pintype "passive"))
      (node (ref "Q3") (pin "6") (pinfunction "D_6") (pintype "passive"))
      (node (ref "Q3") (pin "7") (pinfunction "D_7") (pintype "passive"))
      (node (ref "Q3") (pin "8") (pinfunction "D_8") (pintype "passive"))
      (node (ref "Q3") (pin "PAD") (pinfunction "D_PAD") (pintype "passive"))
      (node (ref "Q5") (pin "5") (pinfunction "D_5") (pintype "passive"))
      (node (ref "Q5") (pin "6") (pinfunction "D_6") (pintype "passive"))
      (node (ref "Q5") (pin "7") (pinfunction "D_7") (pintype "passive"))
      (node (ref "Q5") (pin "8") (pinfunction "D_8") (pintype "passive"))
      (node (ref "Q5") (pin "PAD") (pinfunction "D_PAD") (pintype "passive"))
      (node (ref "R2") (pin "P$2") (pinfunction "P$2_P$2") (pintype "passive"))
      (node (ref "R7") (pin "P$2") (pinfunction "P$2_P$2") (pintype "passive"))
      (node (ref "U2") (pin "47") (pinfunction "VIN_47") (pintype "bidirectional"))
      (node (ref "U2") (pin "6") (pinfunction "VM_6") (pintype "bidirectional"))
      (node (ref "U2") (pin "7") (pinfunction "VDRAIN_7") (pintype "bidirectional"))
      (node (ref "V+") (pin "1") (pinfunction "P$1_1") (pintype "bidirectional"))
    )
    (net (code "69") (name "V-") (class "Default")
      (node (ref "C13") (pin "P$2") (pinfunction "P$2_P$2") (pintype "passive"))
      (node (ref "C14") (pin "P$2") (pinfunction "P$2_P$2") (pintype "passive"))
      (node (ref "C15") (pin "P$2") (pinfunction "P$2_P$2") (pintype "passive"))
      (node (ref "C16") (pin "P$2") (pinfunction "P$2_P$2") (pintype "passive"))
      (node (ref "C17") (pin "P$2") (pinfunction "P$2_P$2") (pintype "passive"))
      (node (ref "C18") (pin "P$2") (pinfunction "P$2_P$2") (pintype "passive"))
      (node (ref "C19") (pin "P$2") (pinfunction "P$2_P$2") (pintype "passive"))
      (node (ref "C28") (pin "P$2") (pinfunction "P$2_P$2") (pintype "passive"))
      (node (ref "D1") (pin "ANODE") (pinfunction "ANODE_ANODE") (pintype "bidirectional"))
      (node (ref "R4") (pin "P$2") (pinfunction "P$2_P$2") (pintype "passive"))
      (node (ref "RA") (pin "1") (pinfunction "1_1") (pintype "passive"))
      (node (ref "RB") (pin "1") (pinfunction "1_1") (pintype "passive"))
      (node (ref "RC") (pin "1") (pinfunction "1_1") (pintype "passive"))
      (node (ref "SH1") (pin "2") (pinfunction "P$2_2") (pintype "bidirectional"))
      (node (ref "SH2") (pin "2") (pinfunction "P$2_2") (pintype "bidirectional"))
      (node (ref "SH3") (pin "2") (pinfunction "P$2_2") (pintype "bidirectional"))
      (node (ref "SH4") (pin "1") (pinfunction "P$1_1") (pintype "bidirectional"))
      (node (ref "U2") (pin "2") (pinfunction "PGND_2") (pintype "bidirectional"))
      (node (ref "U2") (pin "43") (pinfunction "BGND_43") (pintype "bidirectional"))
      (node (ref "U2") (pin "P1") (pinfunction "PAD_P1") (pintype "bidirectional"))
      (node (ref "U2") (pin "P10") (pinfunction "PAD_P10") (pintype "bidirectional"))
      (node (ref "U2") (pin "P11") (pinfunction "PAD_P11") (pintype "bidirectional"))
      (node (ref "U2") (pin "P12") (pinfunction "PAD_P12") (pintype "bidirectional"))
      (node (ref "U2") (pin "P13") (pinfunction "PAD_P13") (pintype "bidirectional"))
      (node (ref "U2") (pin "P14") (pinfunction "PAD_P14") (pintype "bidirectional"))
      (node (ref "U2") (pin "P15") (pinfunction "PAD_P15") (pintype "bidirectional"))
      (node (ref "U2") (pin "P16") (pinfunction "PAD_P16") (pintype "bidirectional"))
      (node (ref "U2") (pin "P17") (pinfunction "PAD_P17") (pintype "bidirectional"))
      (node (ref "U2") (pin "P18") (pinfunction "PAD_P18") (pintype "bidirectional"))
      (node (ref "U2") (pin "P19") (pinfunction "PAD_P19") (pintype "bidirectional"))
      (node (ref "U2") (pin "P2") (pinfunction "PAD_P2") (pintype "bidirectional"))
      (node (ref "U2") (pin "P20") (pinfunction "PAD_P20") (pintype "bidirectional"))
      (node (ref "U2") (pin "P21") (pinfunction "PAD_P21") (pintype "bidirectional"))
      (node (ref "U2") (pin "P22") (pinfunction "PAD_P22") (pintype "bidirectional"))
      (node (ref "U2") (pin "P23") (pinfunction "PAD_P23") (pintype "bidirectional"))
      (node (ref "U2") (pin "P24") (pinfunction "PAD_P24") (pintype "bidirectional"))
      (node (ref "U2") (pin "P25") (pinfunction "PAD_P25") (pintype "bidirectional"))
      (node (ref "U2") (pin "P3") (pinfunction "PAD_P3") (pintype "bidirectional"))
      (node (ref "U2") (pin "P4") (pinfunction "PAD_P4") (pintype "bidirectional"))
      (node (ref "U2") (pin "P5") (pinfunction "PAD_P5") (pintype "bidirectional"))
      (node (ref "U2") (pin "P6") (pinfunction "PAD_P6") (pintype "bidirectional"))
      (node (ref "U2") (pin "P7") (pinfunction "PAD_P7") (pintype "bidirectional"))
      (node (ref "U2") (pin "P8") (pinfunction "PAD_P8") (pintype "bidirectional"))
      (node (ref "U2") (pin "P9") (pinfunction "PAD_P9") (pintype "bidirectional"))
      (node (ref "U2") (pin "PAD") (pinfunction "PAD_PAD") (pintype "bidirectional"))
      (node (ref "V-") (pin "1") (pinfunction "P$1_1") (pintype "bidirectional"))
    )
    (net (code "70") (name "unconnected-(SWD-Pad1)") (class "Default")
      (node (ref "SWD") (pin "1") (pinfunction "1_1") (pintype "passive"))
    )
    (net (code "71") (name "unconnected-(U1-PA15{slash}TIM2_1{slash}UART4_RTS-Pad50)") (class "Default")
      (node (ref "U1") (pin "50") (pinfunction "PA15/TIM2_1/UART4_RTS_50") (pintype "bidirectional"))
    )
    (net (code "72") (name "unconnected-(U1-PB2-BOOT1{slash}TIM2_4{slash}SPI3_MOSI{slash}I3S3_SD-Pad28)") (class "Default")
      (node (ref "U1") (pin "28") (pinfunction "PB2-BOOT1/TIM2_4/SPI3_MOSI/I3S3_SD_28") (pintype "bidirectional"))
    )
    (net (code "73") (name "unconnected-(U1-PB3{slash}SWO{slash}TIM2_2{slash}I2C2_SDA{slash}SPI1_SCK{slash}I2S1_CK{slash}SPI3_SCK{slash}I2S3_CK-Pad55)") (class "Default")
      (node (ref "U1") (pin "55") (pinfunction "PB3/SWO/TIM2_2/I2C2_SDA/SPI1_SCK/I2S1_CK/SPI3_SCK/I2S3_CK_55") (pintype "bidirectional"))
    )
    (net (code "74") (name "unconnected-(U1-PB4{slash}NJTRST{slash}TIM3_1{slash}I2C3_SDA{slash}SPI1_MISO{slash}SPI3_MISO-Pad56)") (class "Default")
      (node (ref "U1") (pin "56") (pinfunction "PB4/NJTRST/TIM3_1/I2C3_SDA/SPI1_MISO/SPI3_MISO_56") (pintype "bidirectional"))
    )
    (net (code "75") (name "unconnected-(U1-PB5{slash}TIM3_2{slash}SPI1_MOSI{slash}I2S1_SD{slash}SPI3_MOSI{slash}I2S3_SD-Pad57)") (class "Default")
      (node (ref "U1") (pin "57") (pinfunction "PB5/TIM3_2/SPI1_MOSI/I2S1_SD/SPI3_MOSI/I2S3_SD_57") (pintype "bidirectional"))
    )
    (net (code "76") (name "unconnected-(U1-PB6{slash}TIM4_1{slash}I2C1_SCL{slash}UART1_TX-Pad58)") (class "Default")
      (node (ref "U1") (pin "58") (pinfunction "PB6/TIM4_1/I2C1_SCL/UART1_TX_58") (pintype "bidirectional"))
    )
    (net (code "77") (name "unconnected-(U1-PB7{slash}TIM4_2{slash}I2C1_SDA{slash}UART1_RX-Pad59)") (class "Default")
      (node (ref "U1") (pin "59") (pinfunction "PB7/TIM4_2/I2C1_SDA/UART1_RX_59") (pintype "bidirectional"))
    )
    (net (code "78") (name "unconnected-(U1-PB10{slash}TIM2_3{slash}I2C2_SCL{slash}SPI3_SCK{slash}I2S2_CK{slash}UART3_TX-Pad29)") (class "Default")
      (node (ref "U1") (pin "29") (pinfunction "PB10/TIM2_3/I2C2_SCL/SPI3_SCK/I2S2_CK/UART3_TX_29") (pintype "bidirectional"))
    )
    (net (code "79") (name "unconnected-(U1-PC2{slash}SPI2_MISO-Pad10)") (class "Default")
      (node (ref "U1") (pin "10") (pinfunction "PC2/SPI2_MISO_10") (pintype "bidirectional"))
    )
    (net (code "80") (name "unconnected-(U1-PC8{slash}TIM3_3{slash}TIM8_3{slash}UART6_CK-Pad39)") (class "Default")
      (node (ref "U1") (pin "39") (pinfunction "PC8/TIM3_3/TIM8_3/UART6_CK_39") (pintype "bidirectional"))
    )
    (net (code "81") (name "unconnected-(U1-PC9{slash}TIM3_4{slash}TIM8_4{slash}I2C3_SDA-Pad40)") (class "Default")
      (node (ref "U1") (pin "40") (pinfunction "PC9/TIM3_4/TIM8_4/I2C3_SDA_40") (pintype "bidirectional"))
    )
    (net (code "82") (name "unconnected-(U1-PC12{slash}I2C2_SDA{slash}SPI3_MOSI{slash}I2S3_SD{slash}UART3_CK{slash}UART5_TX-Pad53)") (class "Default")
      (node (ref "U1") (pin "53") (pinfunction "PC12/I2C2_SDA/SPI3_MOSI/I2S3_SD/UART3_CK/UART5_TX_53") (pintype "bidirectional"))
    )
    (net (code "83") (name "unconnected-(U1-PC13-Pad2)") (class "Default")
      (node (ref "U1") (pin "2") (pinfunction "PC13_2") (pintype "bidirectional"))
    )
    (net (code "84") (name "unconnected-(U1-PC14-Pad3)") (class "Default")
      (node (ref "U1") (pin "3") (pinfunction "PC14_3") (pintype "bidirectional"))
    )
    (net (code "85") (name "unconnected-(U1-PC15-Pad4)") (class "Default")
      (node (ref "U1") (pin "4") (pinfunction "PC15_4") (pintype "bidirectional"))
    )
    (net (code "86") (name "unconnected-(U1-PD2-Pad54)") (class "Default")
      (node (ref "U1") (pin "54") (pinfunction "PD2_54") (pintype "bidirectional"))
    )
    (net (code "87") (name "unconnected-(U2-CAL-Pad34)") (class "Default")
      (node (ref "U2") (pin "34") (pinfunction "CAL_34") (pintype "bidirectional"))
    )
    (net (code "88") (name "unconnected-(U3-PWM-Pad8)") (class "Default")
      (node (ref "U3") (pin "8") (pinfunction "PWM_8") (pintype "bidirectional"))
    )
    (net (code "89") (name "unconnected-(U3-VDD5V-Pad11)") (class "Default")
      (node (ref "U3") (pin "11") (pinfunction "VDD5V_11") (pintype "bidirectional"))
    )
  )
)
